# led.net
KiCad netlist of a schematic drawn in EAGLE
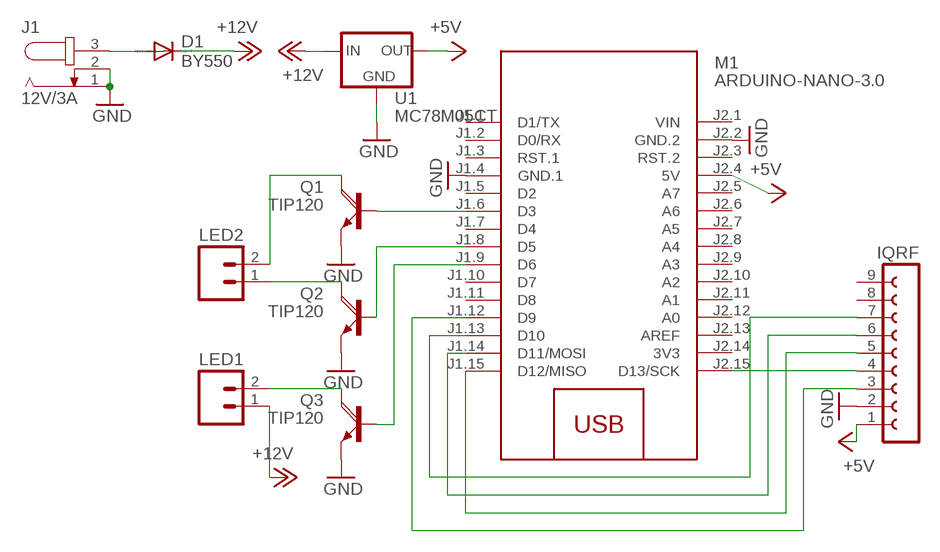
[diagram p0: schematic, sheet 1]

(export (version "E")
  (design (tool "Eeschema 10.0.6"))
  (components
    (comp (ref "D1")
      (value "BY550")
      (footprint "eagle-import:DO27-15")
      (libsource (lib "eagle-import") (part "BY550"))
    )
    (comp (ref "IQRF")
      (value "FE09-1")
      (footprint "eagle-import:FE09")
      (libsource (lib "eagle-import") (part "FE09-1"))
    )
    (comp (ref "J1")
      (value "12V/3A")
      (footprint "eagle-import:SPC4077")
      (libsource (lib "eagle-import") (part "JACK-PLUG0"))
    )
    (comp (ref "LED1")
      (value "M025MM")
      (footprint "eagle-import:SCREWTERMINAL-5MM-2")
      (libsource (lib "eagle-import") (part "M025MM"))
    )
    (comp (ref "LED2")
      (value "M025MM")
      (footprint "eagle-import:SCREWTERMINAL-5MM-2")
      (libsource (lib "eagle-import") (part "M025MM"))
    )
    (comp (ref "M1")
      (value "ARDUINO-NANO-3.0")
      (footprint "eagle-import:ARDUINO-NANO-3.0")
      (libsource (lib "eagle-import") (part "ARDUINO-NANO-3.0"))
    )
    (comp (ref "Q1")
      (value "TIP120")
      (footprint "eagle-import:TO220AH")
      (libsource (lib "eagle-import") (part "TIP120"))
    )
    (comp (ref "Q2")
      (value "TIP120")
      (footprint "eagle-import:TO220AH")
      (libsource (lib "eagle-import") (part "TIP120"))
    )
    (comp (ref "Q3")
      (value "TIP120")
      (footprint "eagle-import:TO220AH")
      (libsource (lib "eagle-import") (part "TIP120"))
    )
    (comp (ref "U1")
      (value "MC78M05CT")
      (footprint "eagle-import:TO-220-ALT")
      (libsource (lib "eagle-import") (part "V_REG_78XX-TO-220"))
    )
  )
  (nets
    (net (code "1") (name "+5V") (class "Default")
      (node (ref "IQRF") (pin "1") (pinfunction "1_1") (pintype "passive"))
      (node (ref "M1") (pin "J2.4") (pinfunction "5V_J2.4") (pintype "power_in"))
      (node (ref "U1") (pin "OUT") (pinfunction "OUT_OUT") (pintype "passive"))
    )
    (net (code "2") (name "+12V") (class "Default")
      (node (ref "D1") (pin "C") (pinfunction "C_C") (pintype "passive"))
      (node (ref "LED1") (pin "1") (pinfunction "1_1") (pintype "passive"))
      (node (ref "U1") (pin "IN") (pinfunction "IN_IN") (pintype "input"))
    )
    (net (code "3") (name "/3V3") (class "Default")
      (node (ref "M1") (pin "J2.14") (pinfunction "3V3_J2.14") (pintype "power_in"))
    )
    (net (code "4") (name "/VIN") (class "Default")
      (node (ref "M1") (pin "J2.1") (pinfunction "VIN_J2.1") (pintype "power_in"))
    )
    (net (code "5") (name "GND") (class "Default")
      (node (ref "IQRF") (pin "2") (pinfunction "2_2") (pintype "passive"))
      (node (ref "J1") (pin "1") (pinfunction "1_1") (pintype "passive"))
      (node (ref "J1") (pin "2") (pinfunction "2_2") (pintype "passive"))
      (node (ref "M1") (pin "J1.4") (pinfunction "GND.1_J1.4") (pintype "power_in"))
      (node (ref "M1") (pin "J2.2") (pinfunction "GND.2_J2.2") (pintype "power_in"))
      (node (ref "Q1") (pin "E") (pinfunction "E_E") (pintype "passive"))
      (node (ref "Q2") (pin "E") (pinfunction "E_E") (pintype "passive"))
      (node (ref "Q3") (pin "E") (pinfunction "E_E") (pintype "passive"))
      (node (ref "U1") (pin "GND") (pinfunction "GND_GND") (pintype "input"))
    )
    (net (code "6") (name "Net-(D1-PadA)") (class "Default")
      (node (ref "D1") (pin "A") (pinfunction "A_A") (pintype "passive"))
      (node (ref "J1") (pin "3") (pinfunction "3_3") (pintype "passive"))
    )
    (net (code "7") (name "Net-(LED1-Pad2)") (class "Default")
      (node (ref "LED1") (pin "2") (pinfunction "2_2") (pintype "passive"))
      (node (ref "Q3") (pin "C") (pinfunction "C_C") (pintype "passive"))
    )
    (net (code "8") (name "Net-(LED2-Pad1)") (class "Default")
      (node (ref "LED2") (pin "1") (pinfunction "1_1") (pintype "passive"))
      (node (ref "Q2") (pin "C") (pinfunction "C_C") (pintype "passive"))
    )
    (net (code "9") (name "Net-(LED2-Pad2)") (class "Default")
      (node (ref "LED2") (pin "2") (pinfunction "2_2") (pintype "passive"))
      (node (ref "Q1") (pin "C") (pinfunction "C_C") (pintype "passive"))
    )
    (net (code "10") (name "Net-(M1-D3)") (class "Default")
      (node (ref "M1") (pin "J1.6") (pinfunction "D3_J1.6") (pintype "bidirectional"))
      (node (ref "Q1") (pin "B") (pinfunction "B_B") (pintype "passive"))
    )
    (net (code "11") (name "Net-(M1-D5)") (class "Default")
      (node (ref "M1") (pin "J1.8") (pinfunction "D5_J1.8") (pintype "bidirectional"))
      (node (ref "Q2") (pin "B") (pinfunction "B_B") (pintype "passive"))
    )
    (net (code "12") (name "Net-(M1-D6)") (class "Default")
      (node (ref "M1") (pin "J1.9") (pinfunction "D6_J1.9") (pintype "bidirectional"))
      (node (ref "Q3") (pin "B") (pinfunction "B_B") (pintype "passive"))
    )
    (net (code "13") (name "Net-(M1-D9)") (class "Default")
      (node (ref "IQRF") (pin "3") (pinfunction "3_3") (pintype "passive"))
      (node (ref "M1") (pin "J1.12") (pinfunction "D9_J1.12") (pintype "bidirectional"))
    )
    (net (code "14") (name "Net-(M1-D10)") (class "Default")
      (node (ref "IQRF") (pin "7") (pinfunction "7_7") (pintype "passive"))
      (node (ref "M1") (pin "J1.13") (pinfunction "D10_J1.13") (pintype "bidirectional"))
    )
    (net (code "15") (name "Net-(M1-D11{slash}MOSI)") (class "Default")
      (node (ref "IQRF") (pin "6") (pinfunction "6_6") (pintype "passive"))
      (node (ref "M1") (pin "J1.14") (pinfunction "D11/MOSI_J1.14") (pintype "bidirectional"))
    )
    (net (code "16") (name "Net-(M1-D12{slash}MISO)") (class "Default")
      (node (ref "IQRF") (pin "5") (pinfunction "5_5") (pintype "passive"))
      (node (ref "M1") (pin "J1.15") (pinfunction "D12/MISO_J1.15") (pintype "bidirectional"))
    )
    (net (code "17") (name "Net-(M1-D13{slash}SCK)") (class "Default")
      (node (ref "IQRF") (pin "4") (pinfunction "4_4") (pintype "passive"))
      (node (ref "M1") (pin "J2.15") (pinfunction "D13/SCK_J2.15") (pintype "bidirectional"))
    )
    (net (code "18") (name "unconnected-(IQRF-Pad8)") (class "Default")
      (node (ref "IQRF") (pin "8") (pinfunction "8_8") (pintype "passive"))
    )
    (net (code "19") (name "unconnected-(IQRF-Pad9)") (class "Default")
      (node (ref "IQRF") (pin "9") (pinfunction "9_9") (pintype "passive"))
    )
    (net (code "20") (name "unconnected-(M1-A0-PadJ2.12)") (class "Default")
      (node (ref "M1") (pin "J2.12") (pinfunction "A0_J2.12") (pintype "bidirectional"))
    )
    (net (code "21") (name "unconnected-(M1-A1-PadJ2.11)") (class "Default")
      (node (ref "M1") (pin "J2.11") (pinfunction "A1_J2.11") (pintype "bidirectional"))
    )
    (net (code "22") (name "unconnected-(M1-A2-PadJ2.10)") (class "Default")
      (node (ref "M1") (pin "J2.10") (pinfunction "A2_J2.10") (pintype "bidirectional"))
    )
    (net (code "23") (name "unconnected-(M1-A3-PadJ2.9)") (class "Default")
      (node (ref "M1") (pin "J2.9") (pinfunction "A3_J2.9") (pintype "bidirectional"))
    )
    (net (code "24") (name "unconnected-(M1-A4-PadJ2.8)") (class "Default")
      (node (ref "M1") (pin "J2.8") (pinfunction "A4_J2.8") (pintype "bidirectional"))
    )
    (net (code "25") (name "unconnected-(M1-A5-PadJ2.7)") (class "Default")
      (node (ref "M1") (pin "J2.7") (pinfunction "A5_J2.7") (pintype "bidirectional"))
    )
    (net (code "26") (name "unconnected-(M1-A6-PadJ2.6)") (class "Default")
      (node (ref "M1") (pin "J2.6") (pinfunction "A6_J2.6") (pintype "bidirectional"))
    )
    (net (code "27") (name "unconnected-(M1-A7-PadJ2.5)") (class "Default")
      (node (ref "M1") (pin "J2.5") (pinfunction "A7_J2.5") (pintype "bidirectional"))
    )
    (net (code "28") (name "unconnected-(M1-AREF-PadJ2.13)") (class "Default")
      (node (ref "M1") (pin "J2.13") (pinfunction "AREF_J2.13") (pintype "bidirectional"))
    )
    (net (code "29") (name "unconnected-(M1-D0{slash}RX-PadJ1.2)") (class "Default")
      (node (ref "M1") (pin "J1.2") (pinfunction "D0/RX_J1.2") (pintype "bidirectional"))
    )
    (net (code "30") (name "unconnected-(M1-D1{slash}TX-PadJ1.1)") (class "Default")
      (node (ref "M1") (pin "J1.1") (pinfunction "D1/TX_J1.1") (pintype "bidirectional"))
    )
    (net (code "31") (name "unconnected-(M1-D2-PadJ1.5)") (class "Default")
      (node (ref "M1") (pin "J1.5") (pinfunction "D2_J1.5") (pintype "bidirectional"))
    )
    (net (code "32") (name "unconnected-(M1-D4-PadJ1.7)") (class "Default")
      (node (ref "M1") (pin "J1.7") (pinfunction "D4_J1.7") (pintype "bidirectional"))
    )
    (net (code "33") (name "unconnected-(M1-D7-PadJ1.10)") (class "Default")
      (node (ref "M1") (pin "J1.10") (pinfunction "D7_J1.10") (pintype "bidirectional"))
    )
    (net (code "34") (name "unconnected-(M1-D8-PadJ1.11)") (class "Default")
      (node (ref "M1") (pin "J1.11") (pinfunction "D8_J1.11") (pintype "bidirectional"))
    )
    (net (code "35") (name "unconnected-(M1-RST.1-PadJ1.3)") (class "Default")
      (node (ref "M1") (pin "J1.3") (pinfunction "RST.1_J1.3") (pintype "bidirectional"))
    )
    (net (code "36") (name "unconnected-(M1-RST.2-PadJ2.3)") (class "Default")
      (node (ref "M1") (pin "J2.3") (pinfunction "RST.2_J2.3") (pintype "bidirectional"))
    )
  )
)
